# shield_lcd1.net
KiCad netlist of a schematic drawn in EAGLE
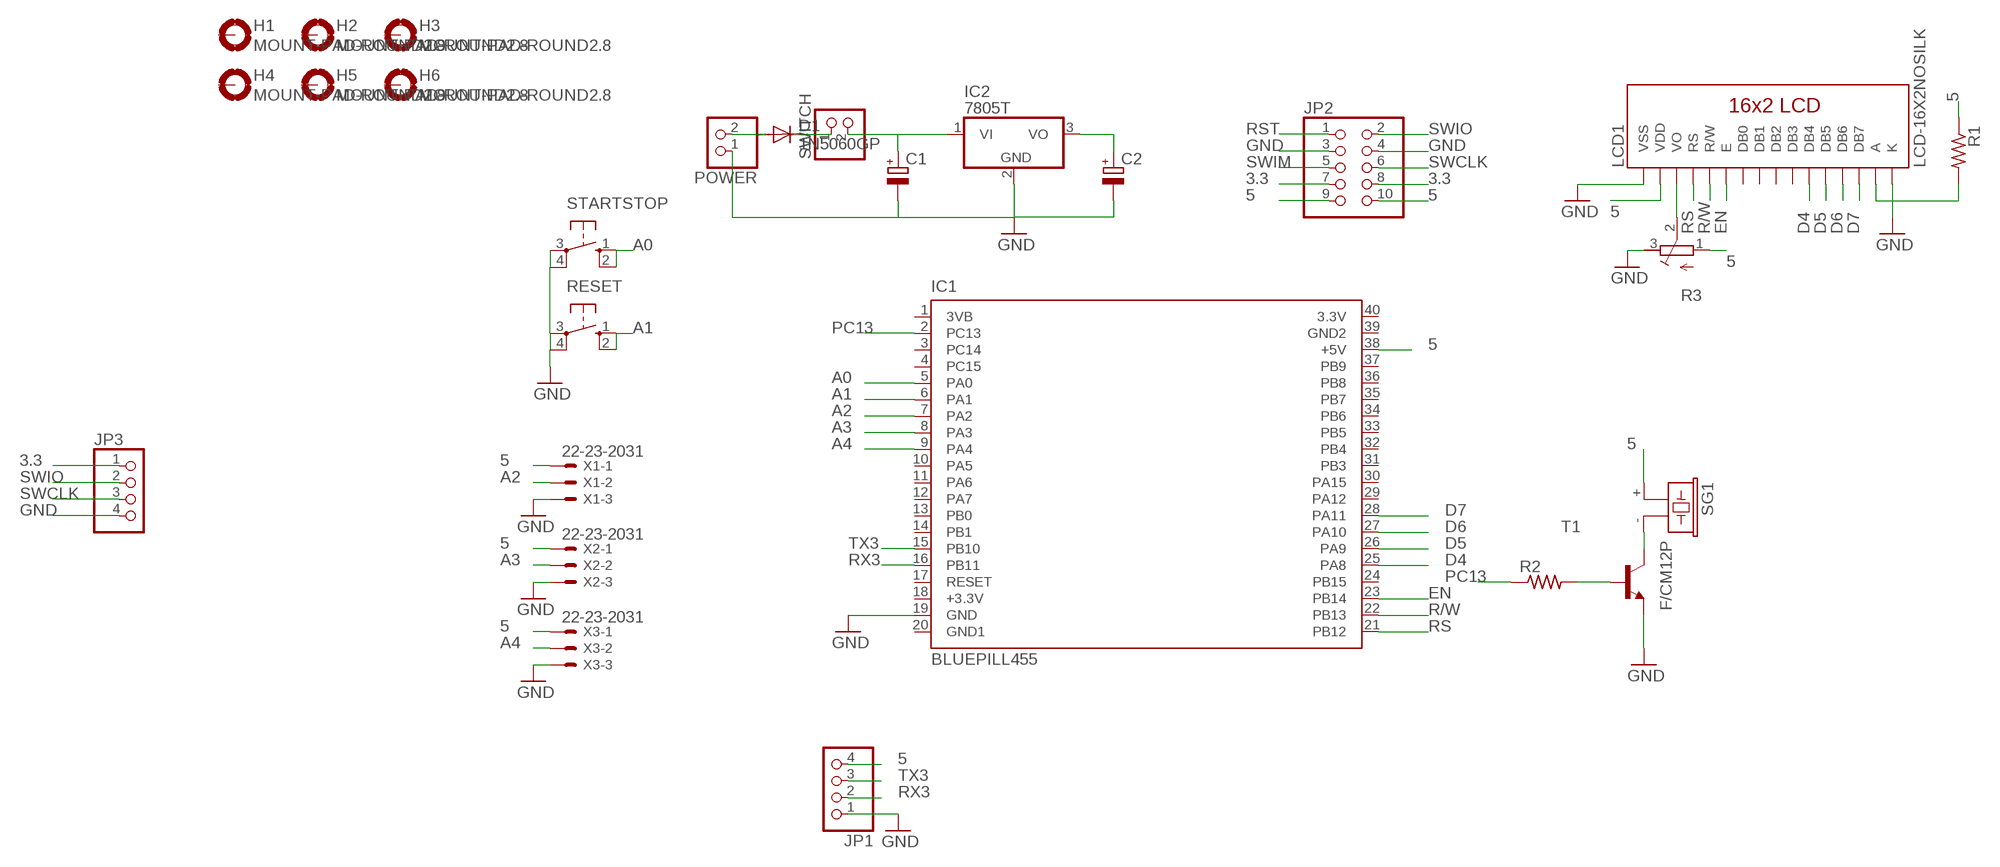
[diagram p0: schematic, sheet 1]

(export (version "E")
  (design (tool "Eeschema 10.0.6"))
  (components
    (comp (ref "C1")
      (value "CPOL-EUE2.5-7")
      (footprint "eagle-import:E2,5-7")
      (libsource (lib "eagle-import") (part "CPOL-EUE2.5-7"))
    )
    (comp (ref "C2")
      (value "CPOL-EUE2.5-6")
      (footprint "eagle-import:E2,5-6")
      (libsource (lib "eagle-import") (part "CPOL-EUE2.5-6"))
    )
    (comp (ref "D1")
      (value "1N5060GP")
      (footprint "eagle-import:DO15-12")
      (libsource (lib "eagle-import") (part "1N5060GP"))
    )
    (comp (ref "H1")
      (value "MOUNT-PAD-ROUND2.8")
      (footprint "eagle-import:2,8-PAD")
      (libsource (lib "eagle-import") (part "MOUNT-PAD-ROUND2.8"))
    )
    (comp (ref "H2")
      (value "MOUNT-PAD-ROUND2.8")
      (footprint "eagle-import:2,8-PAD")
      (libsource (lib "eagle-import") (part "MOUNT-PAD-ROUND2.8"))
    )
    (comp (ref "H3")
      (value "MOUNT-PAD-ROUND2.8")
      (footprint "eagle-import:2,8-PAD")
      (libsource (lib "eagle-import") (part "MOUNT-PAD-ROUND2.8"))
    )
    (comp (ref "H4")
      (value "MOUNT-PAD-ROUND2.8")
      (footprint "eagle-import:2,8-PAD")
      (libsource (lib "eagle-import") (part "MOUNT-PAD-ROUND2.8"))
    )
    (comp (ref "H5")
      (value "MOUNT-PAD-ROUND2.8")
      (footprint "eagle-import:2,8-PAD")
      (libsource (lib "eagle-import") (part "MOUNT-PAD-ROUND2.8"))
    )
    (comp (ref "H6")
      (value "MOUNT-PAD-ROUND2.8")
      (footprint "eagle-import:2,8-PAD")
      (libsource (lib "eagle-import") (part "MOUNT-PAD-ROUND2.8"))
    )
    (comp (ref "IC1")
      (value "BLUEPILL455")
      (footprint "eagle-import:DIL40")
      (fields (field (name "MF") "BluePill"))
      (libsource (lib "eagle-import") (part "BLUEPILL455"))
    )
    (comp (ref "IC2")
      (value "7805T")
      (footprint "eagle-import:TO220H")
      (libsource (lib "eagle-import") (part "78T05"))
    )
    (comp (ref "JP1")
      (value "PINHD-1X4")
      (footprint "eagle-import:1X04")
      (libsource (lib "eagle-import") (part "PINHD-1X4"))
    )
    (comp (ref "JP2")
      (value "PINHD-2X5")
      (footprint "eagle-import:2X05")
      (libsource (lib "eagle-import") (part "PINHD-2X5"))
    )
    (comp (ref "JP3")
      (value "PINHD-1X4")
      (footprint "eagle-import:1X04")
      (libsource (lib "eagle-import") (part "PINHD-1X4"))
    )
    (comp (ref "LCD1")
      (value "LCD-16X2NOSILK")
      (footprint "eagle-import:LCD-16X2_NOSILK")
      (libsource (lib "eagle-import") (part "LCD-16X2NOSILK"))
    )
    (comp (ref "POWER")
      (value "PINHD-1X2")
      (footprint "eagle-import:1X02")
      (libsource (lib "eagle-import") (part "PINHD-1X2"))
    )
    (comp (ref "R1")
      (value "R-US_0207/10")
      (footprint "eagle-import:0207_10")
      (libsource (lib "eagle-import") (part "R-US_0207/10"))
    )
    (comp (ref "R2")
      (value "R-US_M0805")
      (footprint "eagle-import:M0805")
      (libsource (lib "eagle-import") (part "R-US_M0805"))
    )
    (comp (ref "R3")
      (value "R-TRIMM3339P")
      (footprint "eagle-import:RTRIM3339P")
      (libsource (lib "eagle-import") (part "R-TRIMM3339P"))
    )
    (comp (ref "RESET")
      (value "40-XX")
      (footprint "eagle-import:B3F-40XX")
      (fields (field (name "MF") "OMRON COMPONENTS USA") (field (name "MPN") "B3F-4000"))
      (libsource (lib "eagle-import") (part "40-XX"))
    )
    (comp (ref "SG1")
      (value "F/CM12P")
      (footprint "eagle-import:F_CM12P")
      (libsource (lib "eagle-import") (part "F/CM12P"))
    )
    (comp (ref "STARTSTOP")
      (value "40-XX")
      (footprint "eagle-import:B3F-40XX")
      (fields (field (name "MF") "OMRON COMPONENTS USA") (field (name "MPN") "B3F-4000"))
      (libsource (lib "eagle-import") (part "40-XX"))
    )
    (comp (ref "SWITCH")
      (value "PINHD-1X2")
      (footprint "eagle-import:1X02")
      (libsource (lib "eagle-import") (part "PINHD-1X2"))
    )
    (comp (ref "T1")
      (value "BF820-NPN-SOT23-BEC")
      (footprint "eagle-import:SOT23-BEC")
      (libsource (lib "eagle-import") (part "-NPN-SOT23-BECBF820"))
    )
    (comp (ref "X1")
      (value "22-23-2031")
      (footprint "eagle-import:22-23-2031")
      (fields (field (name "MF") "MOLEX"))
      (libsource (lib "eagle-import") (part "22-23-2031"))
    )
    (comp (ref "X2")
      (value "22-23-2031")
      (footprint "eagle-import:22-23-2031")
      (fields (field (name "MF") "MOLEX"))
      (libsource (lib "eagle-import") (part "22-23-2031"))
    )
    (comp (ref "X3")
      (value "22-23-2031")
      (footprint "eagle-import:22-23-2031")
      (fields (field (name "MF") "MOLEX"))
      (libsource (lib "eagle-import") (part "22-23-2031"))
    )
  )
  (nets
    (net (code "1") (name "/3.3") (class "Default")
      (node (ref "JP2") (pin "7") (pinfunction "7_7") (pintype "passive"))
      (node (ref "JP2") (pin "8") (pinfunction "8_8") (pintype "passive"))
      (node (ref "JP3") (pin "1") (pinfunction "1_1") (pintype "passive"))
    )
    (net (code "2") (name "/5") (class "Default")
      (node (ref "IC1") (pin "38") (pinfunction "+5V_38") (pintype "bidirectional"))
      (node (ref "JP1") (pin "4") (pinfunction "4_4") (pintype "passive"))
      (node (ref "JP2") (pin "10") (pinfunction "10_10") (pintype "passive"))
      (node (ref "JP2") (pin "9") (pinfunction "9_9") (pintype "passive"))
      (node (ref "LCD1") (pin "2") (pinfunction "VDD_2") (pintype "power_in"))
      (node (ref "R1") (pin "1") (pinfunction "1_1") (pintype "passive"))
      (node (ref "R3") (pin "1") (pinfunction "A_1") (pintype "passive"))
      (node (ref "SG1") (pin "+") (pinfunction "1_+") (pintype "passive"))
      (node (ref "X1") (pin "1") (pinfunction "S_1") (pintype "passive"))
      (node (ref "X2") (pin "1") (pinfunction "S_1") (pintype "passive"))
      (node (ref "X3") (pin "1") (pinfunction "S_1") (pintype "passive"))
    )
    (net (code "3") (name "/A0") (class "Default")
      (node (ref "IC1") (pin "5") (pinfunction "PA0_5") (pintype "bidirectional"))
      (node (ref "STARTSTOP") (pin "1") (pinfunction "S_1") (pintype "passive"))
      (node (ref "STARTSTOP") (pin "2") (pinfunction "S1_2") (pintype "passive"))
    )
    (net (code "4") (name "/A1") (class "Default")
      (node (ref "IC1") (pin "6") (pinfunction "PA1_6") (pintype "bidirectional"))
      (node (ref "RESET") (pin "1") (pinfunction "S_1") (pintype "passive"))
      (node (ref "RESET") (pin "2") (pinfunction "S1_2") (pintype "passive"))
    )
    (net (code "5") (name "/A2") (class "Default")
      (node (ref "IC1") (pin "7") (pinfunction "PA2_7") (pintype "bidirectional"))
      (node (ref "X1") (pin "2") (pinfunction "S_2") (pintype "passive"))
    )
    (net (code "6") (name "/A3") (class "Default")
      (node (ref "IC1") (pin "8") (pinfunction "PA3_8") (pintype "bidirectional"))
      (node (ref "X2") (pin "2") (pinfunction "S_2") (pintype "passive"))
    )
    (net (code "7") (name "/A4") (class "Default")
      (node (ref "IC1") (pin "9") (pinfunction "PA4_9") (pintype "bidirectional"))
      (node (ref "X3") (pin "2") (pinfunction "S_2") (pintype "passive"))
    )
    (net (code "8") (name "/D4") (class "Default")
      (node (ref "IC1") (pin "25") (pinfunction "PA8_25") (pintype "bidirectional"))
      (node (ref "LCD1") (pin "11") (pinfunction "DB4_11") (pintype "bidirectional"))
    )
    (net (code "9") (name "/D5") (class "Default")
      (node (ref "IC1") (pin "26") (pinfunction "PA9_26") (pintype "bidirectional"))
      (node (ref "LCD1") (pin "12") (pinfunction "DB5_12") (pintype "bidirectional"))
    )
    (net (code "10") (name "/D6") (class "Default")
      (node (ref "IC1") (pin "27") (pinfunction "PA10_27") (pintype "bidirectional"))
      (node (ref "LCD1") (pin "13") (pinfunction "DB6_13") (pintype "bidirectional"))
    )
    (net (code "11") (name "/D7") (class "Default")
      (node (ref "IC1") (pin "28") (pinfunction "PA11_28") (pintype "bidirectional"))
      (node (ref "LCD1") (pin "14") (pinfunction "DB7_14") (pintype "bidirectional"))
    )
    (net (code "12") (name "/EN") (class "Default")
      (node (ref "IC1") (pin "23") (pinfunction "PB14_23") (pintype "bidirectional"))
      (node (ref "LCD1") (pin "6") (pinfunction "E_6") (pintype "input"))
    )
    (net (code "13") (name "/PA6") (class "Default")
      (node (ref "IC1") (pin "11") (pinfunction "PA6_11") (pintype "power_in"))
    )
    (net (code "14") (name "/PA7") (class "Default")
      (node (ref "IC1") (pin "12") (pinfunction "PA7_12") (pintype "power_in"))
    )
    (net (code "15") (name "/PB3") (class "Default")
      (node (ref "IC1") (pin "31") (pinfunction "PB3_31") (pintype "power_in"))
    )
    (net (code "16") (name "/PB4") (class "Default")
      (node (ref "IC1") (pin "32") (pinfunction "PB4_32") (pintype "power_in"))
    )
    (net (code "17") (name "/PC13") (class "Default")
      (node (ref "IC1") (pin "2") (pinfunction "PC13_2") (pintype "bidirectional"))
      (node (ref "R2") (pin "1") (pinfunction "1_1") (pintype "passive"))
    )
    (net (code "18") (name "/RS") (class "Default")
      (node (ref "IC1") (pin "21") (pinfunction "PB12_21") (pintype "bidirectional"))
      (node (ref "LCD1") (pin "4") (pinfunction "RS_4") (pintype "input"))
    )
    (net (code "19") (name "/RST") (class "Default")
      (node (ref "JP2") (pin "1") (pinfunction "1_1") (pintype "passive"))
    )
    (net (code "20") (name "/RX3") (class "Default")
      (node (ref "IC1") (pin "16") (pinfunction "PB11_16") (pintype "bidirectional"))
      (node (ref "JP1") (pin "2") (pinfunction "2_2") (pintype "passive"))
    )
    (net (code "21") (name "/R{slash}W") (class "Default")
      (node (ref "IC1") (pin "22") (pinfunction "PB13_22") (pintype "bidirectional"))
      (node (ref "LCD1") (pin "5") (pinfunction "R/W_5") (pintype "input"))
    )
    (net (code "22") (name "/SWCLK") (class "Default")
      (node (ref "JP2") (pin "6") (pinfunction "6_6") (pintype "passive"))
      (node (ref "JP3") (pin "3") (pinfunction "3_3") (pintype "passive"))
    )
    (net (code "23") (name "/SWIM") (class "Default")
      (node (ref "JP2") (pin "5") (pinfunction "5_5") (pintype "passive"))
    )
    (net (code "24") (name "/SWIO") (class "Default")
      (node (ref "JP2") (pin "2") (pinfunction "2_2") (pintype "passive"))
      (node (ref "JP3") (pin "2") (pinfunction "2_2") (pintype "passive"))
    )
    (net (code "25") (name "/TX3") (class "Default")
      (node (ref "IC1") (pin "15") (pinfunction "PB10_15") (pintype "bidirectional"))
      (node (ref "JP1") (pin "3") (pinfunction "3_3") (pintype "passive"))
    )
    (net (code "26") (name "GND") (class "Default")
      (node (ref "C1") (pin "-") (pinfunction "-_-") (pintype "passive"))
      (node (ref "C2") (pin "-") (pinfunction "-_-") (pintype "passive"))
      (node (ref "IC1") (pin "19") (pinfunction "GND_19") (pintype "bidirectional"))
      (node (ref "IC2") (pin "2") (pinfunction "GND_2") (pintype "passive"))
      (node (ref "JP1") (pin "1") (pinfunction "1_1") (pintype "passive"))
      (node (ref "JP2") (pin "3") (pinfunction "3_3") (pintype "passive"))
      (node (ref "JP2") (pin "4") (pinfunction "4_4") (pintype "passive"))
      (node (ref "JP3") (pin "4") (pinfunction "4_4") (pintype "passive"))
      (node (ref "LCD1") (pin "1") (pinfunction "VSS_1") (pintype "power_in"))
      (node (ref "LCD1") (pin "16") (pinfunction "K_16") (pintype "power_in"))
      (node (ref "POWER") (pin "1") (pinfunction "1_1") (pintype "passive"))
      (node (ref "R3") (pin "3") (pinfunction "E_3") (pintype "passive"))
      (node (ref "RESET") (pin "3") (pinfunction "P_3") (pintype "passive"))
      (node (ref "RESET") (pin "4") (pinfunction "P1_4") (pintype "passive"))
      (node (ref "STARTSTOP") (pin "3") (pinfunction "P_3") (pintype "passive"))
      (node (ref "STARTSTOP") (pin "4") (pinfunction "P1_4") (pintype "passive"))
      (node (ref "T1") (pin "E") (pinfunction "E_E") (pintype "passive"))
      (node (ref "X1") (pin "3") (pinfunction "S_3") (pintype "passive"))
      (node (ref "X2") (pin "3") (pinfunction "S_3") (pintype "passive"))
      (node (ref "X3") (pin "3") (pinfunction "S_3") (pintype "passive"))
    )
    (net (code "27") (name "Net-(D1-PadA)") (class "Default")
      (node (ref "D1") (pin "A") (pinfunction "A_A") (pintype "passive"))
      (node (ref "POWER") (pin "2") (pinfunction "2_2") (pintype "passive"))
    )
    (net (code "28") (name "Net-(D1-PadC)") (class "Default")
      (node (ref "D1") (pin "C") (pinfunction "C_C") (pintype "passive"))
      (node (ref "SWITCH") (pin "1") (pinfunction "1_1") (pintype "passive"))
    )
    (net (code "29") (name "Net-(IC2-VI)") (class "Default")
      (node (ref "C1") (pin "+") (pinfunction "+_+") (pintype "passive"))
      (node (ref "IC2") (pin "1") (pinfunction "VI_1") (pintype "input"))
      (node (ref "SWITCH") (pin "2") (pinfunction "2_2") (pintype "passive"))
    )
    (net (code "30") (name "Net-(IC2-VO)") (class "Default")
      (node (ref "C2") (pin "+") (pinfunction "+_+") (pintype "passive"))
      (node (ref "IC2") (pin "3") (pinfunction "VO_3") (pintype "passive"))
    )
    (net (code "31") (name "Net-(LCD1-A)") (class "Default")
      (node (ref "LCD1") (pin "15") (pinfunction "A_15") (pintype "power_in"))
      (node (ref "R1") (pin "2") (pinfunction "2_2") (pintype "passive"))
    )
    (net (code "32") (name "Net-(LCD1-VO)") (class "Default")
      (node (ref "LCD1") (pin "3") (pinfunction "VO_3") (pintype "bidirectional"))
      (node (ref "R3") (pin "2") (pinfunction "S_2") (pintype "passive"))
    )
    (net (code "33") (name "Net-(R2-Pad2)") (class "Default")
      (node (ref "R2") (pin "2") (pinfunction "2_2") (pintype "passive"))
      (node (ref "T1") (pin "B") (pinfunction "B_B") (pintype "passive"))
    )
    (net (code "34") (name "Net-(SG1-2)") (class "Default")
      (node (ref "SG1") (pin "-") (pinfunction "2_-") (pintype "passive"))
      (node (ref "T1") (pin "C") (pinfunction "C_C") (pintype "passive"))
    )
    (net (code "35") (name "unconnected-(H1-MOUNT-PadB2,8)") (class "Default")
      (node (ref "H1") (pin "B2,8") (pinfunction "MOUNT_B2,8") (pintype "passive"))
    )
    (net (code "36") (name "unconnected-(H2-MOUNT-PadB2,8)") (class "Default")
      (node (ref "H2") (pin "B2,8") (pinfunction "MOUNT_B2,8") (pintype "passive"))
    )
    (net (code "37") (name "unconnected-(H3-MOUNT-PadB2,8)") (class "Default")
      (node (ref "H3") (pin "B2,8") (pinfunction "MOUNT_B2,8") (pintype "passive"))
    )
    (net (code "38") (name "unconnected-(H4-MOUNT-PadB2,8)") (class "Default")
      (node (ref "H4") (pin "B2,8") (pinfunction "MOUNT_B2,8") (pintype "passive"))
    )
    (net (code "39") (name "unconnected-(H5-MOUNT-PadB2,8)") (class "Default")
      (node (ref "H5") (pin "B2,8") (pinfunction "MOUNT_B2,8") (pintype "passive"))
    )
    (net (code "40") (name "unconnected-(H6-MOUNT-PadB2,8)") (class "Default")
      (node (ref "H6") (pin "B2,8") (pinfunction "MOUNT_B2,8") (pintype "passive"))
    )
    (net (code "41") (name "unconnected-(IC1-+3.3V-Pad18)") (class "Default")
      (node (ref "IC1") (pin "18") (pinfunction "+3.3V_18") (pintype "bidirectional"))
    )
    (net (code "42") (name "unconnected-(IC1-3.3V-Pad40)") (class "Default")
      (node (ref "IC1") (pin "40") (pinfunction "3.3V_40") (pintype "bidirectional"))
    )
    (net (code "43") (name "unconnected-(IC1-3VB-Pad1)") (class "Default")
      (node (ref "IC1") (pin "1") (pinfunction "3VB_1") (pintype "input"))
    )
    (net (code "44") (name "unconnected-(IC1-GND1-Pad20)") (class "Default")
      (node (ref "IC1") (pin "20") (pinfunction "GND1_20") (pintype "bidirectional"))
    )
    (net (code "45") (name "unconnected-(IC1-GND2-Pad39)") (class "Default")
      (node (ref "IC1") (pin "39") (pinfunction "GND2_39") (pintype "bidirectional"))
    )
    (net (code "46") (name "unconnected-(IC1-PA5-Pad10)") (class "Default")
      (node (ref "IC1") (pin "10") (pinfunction "PA5_10") (pintype "bidirectional"))
    )
    (net (code "47") (name "unconnected-(IC1-PA12-Pad29)") (class "Default")
      (node (ref "IC1") (pin "29") (pinfunction "PA12_29") (pintype "bidirectional"))
    )
    (net (code "48") (name "unconnected-(IC1-PA15-Pad30)") (class "Default")
      (node (ref "IC1") (pin "30") (pinfunction "PA15_30") (pintype "bidirectional"))
    )
    (net (code "49") (name "unconnected-(IC1-PB0-Pad13)") (class "Default")
      (node (ref "IC1") (pin "13") (pinfunction "PB0_13") (pintype "input"))
    )
    (net (code "50") (name "unconnected-(IC1-PB1-Pad14)") (class "Default")
      (node (ref "IC1") (pin "14") (pinfunction "PB1_14") (pintype "output"))
    )
    (net (code "51") (name "unconnected-(IC1-PB5-Pad33)") (class "Default")
      (node (ref "IC1") (pin "33") (pinfunction "PB5_33") (pintype "bidirectional"))
    )
    (net (code "52") (name "unconnected-(IC1-PB6-Pad34)") (class "Default")
      (node (ref "IC1") (pin "34") (pinfunction "PB6_34") (pintype "bidirectional"))
    )
    (net (code "53") (name "unconnected-(IC1-PB7-Pad35)") (class "Default")
      (node (ref "IC1") (pin "35") (pinfunction "PB7_35") (pintype "bidirectional"))
    )
    (net (code "54") (name "unconnected-(IC1-PB8-Pad36)") (class "Default")
      (node (ref "IC1") (pin "36") (pinfunction "PB8_36") (pintype "bidirectional"))
    )
    (net (code "55") (name "unconnected-(IC1-PB9-Pad37)") (class "Default")
      (node (ref "IC1") (pin "37") (pinfunction "PB9_37") (pintype "bidirectional"))
    )
    (net (code "56") (name "unconnected-(IC1-PB15-Pad24)") (class "Default")
      (node (ref "IC1") (pin "24") (pinfunction "PB15_24") (pintype "bidirectional"))
    )
    (net (code "57") (name "unconnected-(IC1-PC14-Pad3)") (class "Default")
      (node (ref "IC1") (pin "3") (pinfunction "PC14_3") (pintype "bidirectional"))
    )
    (net (code "58") (name "unconnected-(IC1-PC15-Pad4)") (class "Default")
      (node (ref "IC1") (pin "4") (pinfunction "PC15_4") (pintype "bidirectional"))
    )
    (net (code "59") (name "unconnected-(IC1-RESET-Pad17)") (class "Default")
      (node (ref "IC1") (pin "17") (pinfunction "RESET_17") (pintype "bidirectional"))
    )
    (net (code "60") (name "unconnected-(LCD1-DB0-Pad7)") (class "Default")
      (node (ref "LCD1") (pin "7") (pinfunction "DB0_7") (pintype "bidirectional"))
    )
    (net (code "61") (name "unconnected-(LCD1-DB1-Pad8)") (class "Default")
      (node (ref "LCD1") (pin "8") (pinfunction "DB1_8") (pintype "bidirectional"))
    )
    (net (code "62") (name "unconnected-(LCD1-DB2-Pad9)") (class "Default")
      (node (ref "LCD1") (pin "9") (pinfunction "DB2_9") (pintype "bidirectional"))
    )
    (net (code "63") (name "unconnected-(LCD1-DB3-Pad10)") (class "Default")
      (node (ref "LCD1") (pin "10") (pinfunction "DB3_10") (pintype "bidirectional"))
    )
  )
)
